# nChannel.net
KiCad netlist of a schematic drawn in EAGLE
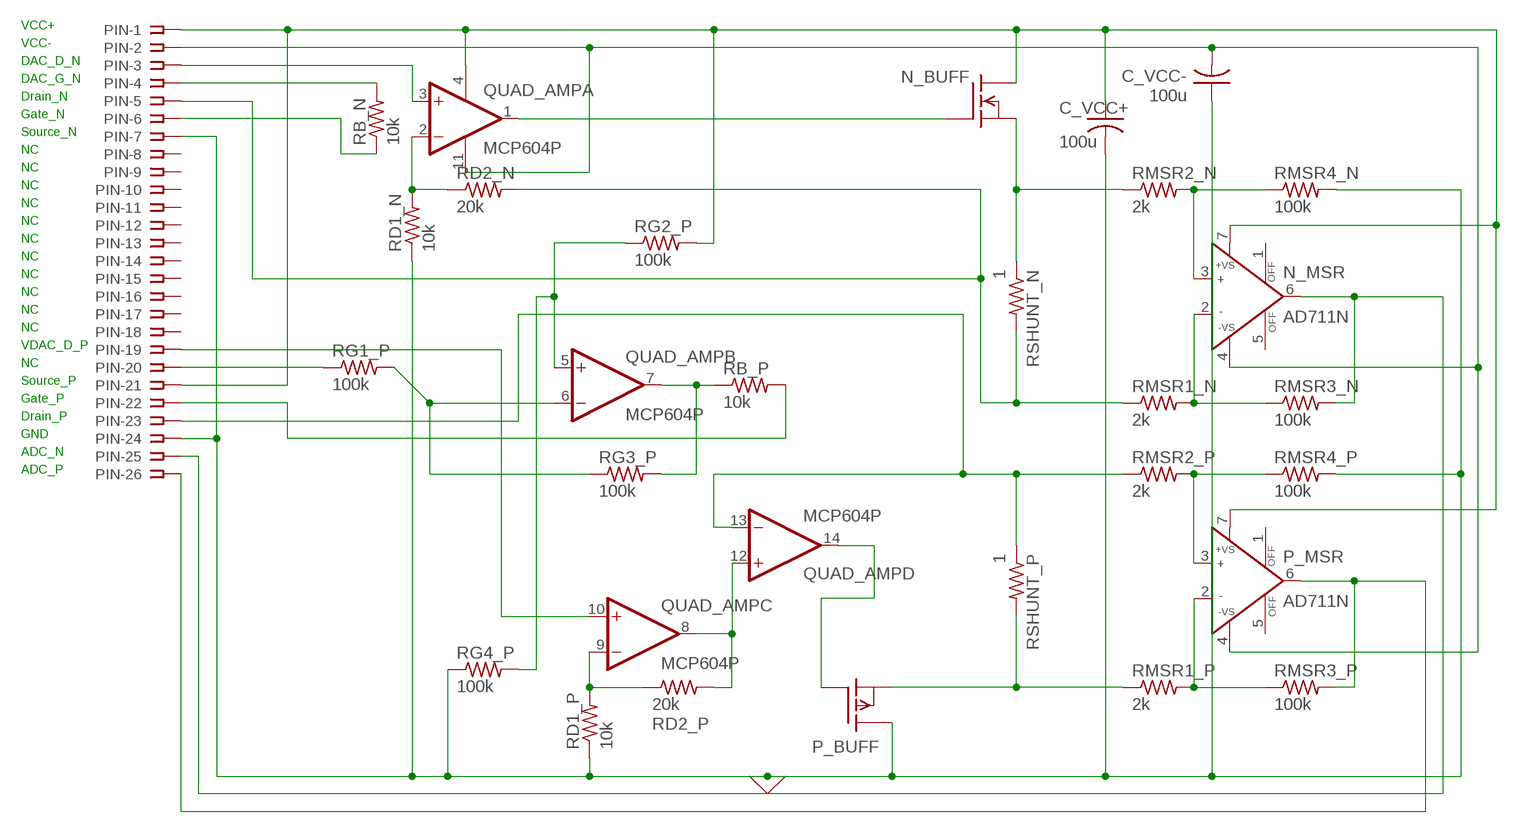
[diagram p0: schematic, sheet 1]

(export (version "E")
  (design (tool "Eeschema 10.0.6"))
  (components
    (comp (ref "C_VCC+")
      (value "100u")
      (footprint "eagle-import:C025-024X044")
      (libsource (lib "eagle-import") (part "C-US025-024X044"))
    )
    (comp (ref "C_VCC-")
      (value "100u")
      (footprint "eagle-import:C025-024X044")
      (libsource (lib "eagle-import") (part "C-US025-024X044"))
    )
    (comp (ref "N_BUFF")
      (value "BSS101")
      (footprint "eagle-import:TO92")
      (libsource (lib "eagle-import") (part "BSS101"))
    )
    (comp (ref "N_MSR")
      (value "AD711N")
      (footprint "eagle-import:DIL08")
      (fields (field (name "MPN") "AD711BQ"))
      (libsource (lib "eagle-import") (part "AD711N"))
    )
    (comp (ref "PIN")
      (value "SSW-126-02-G-S")
      (footprint "eagle-import:SSW-126-02-G-S")
      (fields (field (name "MF") "Samtec Inc."))
      (libsource (lib "eagle-import") (part "SSW-126-02-G-S"))
    )
    (comp (ref "P_BUFF")
      (value "BSS110")
      (footprint "eagle-import:TO92")
      (libsource (lib "eagle-import") (part "BSS110"))
    )
    (comp (ref "P_MSR")
      (value "AD711N")
      (footprint "eagle-import:DIL08")
      (fields (field (name "MPN") "AD711BQ"))
      (libsource (lib "eagle-import") (part "AD711N"))
    )
    (comp (ref "QUAD_AMP")
      (value "MCP604P")
      (footprint "eagle-import:DIL14")
      (libsource (lib "eagle-import") (part "MCP604P"))
    )
    (comp (ref "RB_N")
      (value "10k")
      (footprint "eagle-import:0204_5")
      (libsource (lib "eagle-import") (part "R-US_0204/5"))
    )
    (comp (ref "RB_P")
      (value "10k")
      (footprint "eagle-import:0204_5")
      (libsource (lib "eagle-import") (part "R-US_0204/5"))
    )
    (comp (ref "RD1_N")
      (value "10k")
      (footprint "eagle-import:0204_5")
      (libsource (lib "eagle-import") (part "R-US_0204/5"))
    )
    (comp (ref "RD1_P")
      (value "10k")
      (footprint "eagle-import:0204_5")
      (libsource (lib "eagle-import") (part "R-US_0204/5"))
    )
    (comp (ref "RD2_N")
      (value "20k")
      (footprint "eagle-import:0204_5")
      (libsource (lib "eagle-import") (part "R-US_0204/5"))
    )
    (comp (ref "RD2_P")
      (value "20k")
      (footprint "eagle-import:0204_5")
      (libsource (lib "eagle-import") (part "R-US_0204/5"))
    )
    (comp (ref "RG1_P")
      (value "100k")
      (footprint "eagle-import:0204_5")
      (libsource (lib "eagle-import") (part "R-US_0204/5"))
    )
    (comp (ref "RG2_P")
      (value "100k")
      (footprint "eagle-import:0204_5")
      (libsource (lib "eagle-import") (part "R-US_0204/5"))
    )
    (comp (ref "RG3_P")
      (value "100k")
      (footprint "eagle-import:0204_5")
      (libsource (lib "eagle-import") (part "R-US_0204/5"))
    )
    (comp (ref "RG4_P")
      (value "100k")
      (footprint "eagle-import:0204_5")
      (libsource (lib "eagle-import") (part "R-US_0204/5"))
    )
    (comp (ref "RMSR1_N")
      (value "2k")
      (footprint "eagle-import:0204_5")
      (libsource (lib "eagle-import") (part "R-US_0204/5"))
    )
    (comp (ref "RMSR1_P")
      (value "2k")
      (footprint "eagle-import:0204_5")
      (libsource (lib "eagle-import") (part "R-US_0204/5"))
    )
    (comp (ref "RMSR2_N")
      (value "2k")
      (footprint "eagle-import:0204_5")
      (libsource (lib "eagle-import") (part "R-US_0204/5"))
    )
    (comp (ref "RMSR2_P")
      (value "2k")
      (footprint "eagle-import:0204_5")
      (libsource (lib "eagle-import") (part "R-US_0204/5"))
    )
    (comp (ref "RMSR3_N")
      (value "100k")
      (footprint "eagle-import:0204_5")
      (libsource (lib "eagle-import") (part "R-US_0204/5"))
    )
    (comp (ref "RMSR3_P")
      (value "100k")
      (footprint "eagle-import:0204_5")
      (libsource (lib "eagle-import") (part "R-US_0204/5"))
    )
    (comp (ref "RMSR4_N")
      (value "100k")
      (footprint "eagle-import:0204_5")
      (libsource (lib "eagle-import") (part "R-US_0204/5"))
    )
    (comp (ref "RMSR4_P")
      (value "100k")
      (footprint "eagle-import:0204_5")
      (libsource (lib "eagle-import") (part "R-US_0204/5"))
    )
    (comp (ref "RSHUNT_N")
      (value "1")
      (footprint "eagle-import:0204_5")
      (fields (field (name "SPICEPREFIX") "52"))
      (libsource (lib "eagle-import") (part "R-US_0204/5"))
    )
    (comp (ref "RSHUNT_P")
      (value "1")
      (footprint "eagle-import:0204_5")
      (fields (field (name "SPICEPREFIX") "52"))
      (libsource (lib "eagle-import") (part "R-US_0204/5"))
    )
  )
  (nets
    (net (code "1") (name "GND") (class "Default")
      (node (ref "C_VCC+") (pin "2") (pinfunction "2_2") (pintype "passive"))
      (node (ref "C_VCC-") (pin "1") (pinfunction "1_1") (pintype "passive"))
      (node (ref "PIN") (pin "24") (pinfunction "1_24") (pintype "passive"))
      (node (ref "PIN") (pin "7") (pinfunction "1_7") (pintype "passive"))
      (node (ref "P_BUFF") (pin "3") (pinfunction "D_3") (pintype "passive"))
      (node (ref "RD1_N") (pin "1") (pinfunction "1_1") (pintype "passive"))
      (node (ref "RD1_P") (pin "1") (pinfunction "1_1") (pintype "passive"))
      (node (ref "RG4_P") (pin "1") (pinfunction "1_1") (pintype "passive"))
      (node (ref "RMSR4_N") (pin "2") (pinfunction "2_2") (pintype "passive"))
      (node (ref "RMSR4_P") (pin "2") (pinfunction "2_2") (pintype "passive"))
    )
    (net (code "2") (name "Net-(N_BUFF-D)") (class "Default")
      (node (ref "C_VCC+") (pin "1") (pinfunction "1_1") (pintype "passive"))
      (node (ref "N_BUFF") (pin "3") (pinfunction "D_3") (pintype "passive"))
      (node (ref "N_MSR") (pin "7") (pinfunction "+VS_7") (pintype "input"))
      (node (ref "PIN") (pin "1") (pinfunction "1_1") (pintype "passive"))
      (node (ref "PIN") (pin "21") (pinfunction "1_21") (pintype "passive"))
      (node (ref "P_MSR") (pin "7") (pinfunction "+VS_7") (pintype "input"))
      (node (ref "QUAD_AMP") (pin "4") (pinfunction "V+_4") (pintype "power_in"))
      (node (ref "RG2_P") (pin "2") (pinfunction "2_2") (pintype "passive"))
    )
    (net (code "3") (name "Net-(N_BUFF-G)") (class "Default")
      (node (ref "N_BUFF") (pin "2") (pinfunction "G_2") (pintype "passive"))
      (node (ref "QUAD_AMP") (pin "1") (pinfunction "OUT_1") (pintype "output"))
    )
    (net (code "4") (name "Net-(N_BUFF-S)") (class "Default")
      (node (ref "N_BUFF") (pin "1") (pinfunction "S_1") (pintype "passive"))
      (node (ref "RMSR2_N") (pin "1") (pinfunction "1_1") (pintype "passive"))
      (node (ref "RSHUNT_N") (pin "1") (pinfunction "1_1") (pintype "passive"))
    )
    (net (code "5") (name "Net-(N_MSR--VS)") (class "Default")
      (node (ref "C_VCC-") (pin "2") (pinfunction "2_2") (pintype "passive"))
      (node (ref "N_MSR") (pin "4") (pinfunction "-VS_4") (pintype "input"))
      (node (ref "PIN") (pin "2") (pinfunction "1_2") (pintype "passive"))
      (node (ref "P_MSR") (pin "4") (pinfunction "-VS_4") (pintype "input"))
      (node (ref "QUAD_AMP") (pin "11") (pinfunction "V-_11") (pintype "power_in"))
    )
    (net (code "6") (name "Net-(N_MSR-IN+)") (class "Default")
      (node (ref "N_MSR") (pin "3") (pinfunction "IN+_3") (pintype "input"))
      (node (ref "RMSR2_N") (pin "2") (pinfunction "2_2") (pintype "passive"))
      (node (ref "RMSR4_N") (pin "1") (pinfunction "1_1") (pintype "passive"))
    )
    (net (code "7") (name "Net-(N_MSR-IN-)") (class "Default")
      (node (ref "N_MSR") (pin "2") (pinfunction "IN-_2") (pintype "input"))
      (node (ref "RMSR1_N") (pin "2") (pinfunction "2_2") (pintype "passive"))
      (node (ref "RMSR3_N") (pin "1") (pinfunction "1_1") (pintype "passive"))
    )
    (net (code "8") (name "Net-(N_MSR-OUT)") (class "Default")
      (node (ref "N_MSR") (pin "6") (pinfunction "OUT_6") (pintype "output"))
      (node (ref "PIN") (pin "25") (pinfunction "1_25") (pintype "passive"))
      (node (ref "RMSR3_N") (pin "2") (pinfunction "2_2") (pintype "passive"))
    )
    (net (code "9") (name "Net-(PINK-1)") (class "Default")
      (node (ref "PIN") (pin "19") (pinfunction "1_19") (pintype "passive"))
      (node (ref "QUAD_AMP") (pin "10") (pinfunction "+IN_10") (pintype "input"))
    )
    (net (code "10") (name "Net-(PINM-1)") (class "Default")
      (node (ref "PIN") (pin "20") (pinfunction "1_20") (pintype "passive"))
      (node (ref "RG1_P") (pin "1") (pinfunction "1_1") (pintype "passive"))
    )
    (net (code "11") (name "Net-(PINO-1)") (class "Default")
      (node (ref "PIN") (pin "22") (pinfunction "1_22") (pintype "passive"))
      (node (ref "RB_P") (pin "2") (pinfunction "2_2") (pintype "passive"))
    )
    (net (code "12") (name "Net-(PINP-1)") (class "Default")
      (node (ref "PIN") (pin "23") (pinfunction "1_23") (pintype "passive"))
      (node (ref "QUAD_AMP") (pin "13") (pinfunction "-IN_13") (pintype "input"))
      (node (ref "RMSR2_P") (pin "1") (pinfunction "1_1") (pintype "passive"))
      (node (ref "RSHUNT_P") (pin "1") (pinfunction "1_1") (pintype "passive"))
    )
    (net (code "13") (name "Net-(PINS-1)") (class "Default")
      (node (ref "PIN") (pin "26") (pinfunction "1_26") (pintype "passive"))
      (node (ref "P_MSR") (pin "6") (pinfunction "OUT_6") (pintype "output"))
      (node (ref "RMSR3_P") (pin "2") (pinfunction "2_2") (pintype "passive"))
    )
    (net (code "14") (name "Net-(PINT-1)") (class "Default")
      (node (ref "PIN") (pin "3") (pinfunction "1_3") (pintype "passive"))
      (node (ref "QUAD_AMP") (pin "3") (pinfunction "+IN_3") (pintype "input"))
    )
    (net (code "15") (name "Net-(PINU-1)") (class "Default")
      (node (ref "PIN") (pin "4") (pinfunction "1_4") (pintype "passive"))
      (node (ref "RB_N") (pin "2") (pinfunction "2_2") (pintype "passive"))
    )
    (net (code "16") (name "Net-(PINV-1)") (class "Default")
      (node (ref "PIN") (pin "5") (pinfunction "1_5") (pintype "passive"))
      (node (ref "RD2_N") (pin "2") (pinfunction "2_2") (pintype "passive"))
      (node (ref "RMSR1_N") (pin "1") (pinfunction "1_1") (pintype "passive"))
      (node (ref "RSHUNT_N") (pin "2") (pinfunction "2_2") (pintype "passive"))
    )
    (net (code "17") (name "Net-(PINW-1)") (class "Default")
      (node (ref "PIN") (pin "6") (pinfunction "1_6") (pintype "passive"))
      (node (ref "RB_N") (pin "1") (pinfunction "1_1") (pintype "passive"))
    )
    (net (code "18") (name "Net-(P_BUFF-G)") (class "Default")
      (node (ref "P_BUFF") (pin "2") (pinfunction "G_2") (pintype "passive"))
      (node (ref "QUAD_AMP") (pin "14") (pinfunction "OUT_14") (pintype "output"))
    )
    (net (code "19") (name "Net-(P_BUFF-S)") (class "Default")
      (node (ref "P_BUFF") (pin "1") (pinfunction "S_1") (pintype "passive"))
      (node (ref "RMSR1_P") (pin "1") (pinfunction "1_1") (pintype "passive"))
      (node (ref "RSHUNT_P") (pin "2") (pinfunction "2_2") (pintype "passive"))
    )
    (net (code "20") (name "Net-(P_MSR-IN+)") (class "Default")
      (node (ref "P_MSR") (pin "3") (pinfunction "IN+_3") (pintype "input"))
      (node (ref "RMSR2_P") (pin "2") (pinfunction "2_2") (pintype "passive"))
      (node (ref "RMSR4_P") (pin "1") (pinfunction "1_1") (pintype "passive"))
    )
    (net (code "21") (name "Net-(P_MSR-IN-)") (class "Default")
      (node (ref "P_MSR") (pin "2") (pinfunction "IN-_2") (pintype "input"))
      (node (ref "RMSR1_P") (pin "2") (pinfunction "2_2") (pintype "passive"))
      (node (ref "RMSR3_P") (pin "1") (pinfunction "1_1") (pintype "passive"))
    )
    (net (code "22") (name "Net-(QUAD_AMPA--IN)") (class "Default")
      (node (ref "QUAD_AMP") (pin "2") (pinfunction "-IN_2") (pintype "input"))
      (node (ref "RD1_N") (pin "2") (pinfunction "2_2") (pintype "passive"))
      (node (ref "RD2_N") (pin "1") (pinfunction "1_1") (pintype "passive"))
    )
    (net (code "23") (name "Net-(QUAD_AMPB-+IN)") (class "Default")
      (node (ref "QUAD_AMP") (pin "5") (pinfunction "+IN_5") (pintype "input"))
      (node (ref "RG2_P") (pin "1") (pinfunction "1_1") (pintype "passive"))
      (node (ref "RG4_P") (pin "2") (pinfunction "2_2") (pintype "passive"))
    )
    (net (code "24") (name "Net-(QUAD_AMPB--IN)") (class "Default")
      (node (ref "QUAD_AMP") (pin "6") (pinfunction "-IN_6") (pintype "input"))
      (node (ref "RG1_P") (pin "2") (pinfunction "2_2") (pintype "passive"))
      (node (ref "RG3_P") (pin "1") (pinfunction "1_1") (pintype "passive"))
    )
    (net (code "25") (name "Net-(QUAD_AMPB-OUT)") (class "Default")
      (node (ref "QUAD_AMP") (pin "7") (pinfunction "OUT_7") (pintype "output"))
      (node (ref "RB_P") (pin "1") (pinfunction "1_1") (pintype "passive"))
      (node (ref "RG3_P") (pin "2") (pinfunction "2_2") (pintype "passive"))
    )
    (net (code "26") (name "Net-(QUAD_AMPC--IN)") (class "Default")
      (node (ref "QUAD_AMP") (pin "9") (pinfunction "-IN_9") (pintype "input"))
      (node (ref "RD1_P") (pin "2") (pinfunction "2_2") (pintype "passive"))
      (node (ref "RD2_P") (pin "1") (pinfunction "1_1") (pintype "passive"))
    )
    (net (code "27") (name "Net-(QUAD_AMPC-OUT)") (class "Default")
      (node (ref "QUAD_AMP") (pin "12") (pinfunction "+IN_12") (pintype "input"))
      (node (ref "QUAD_AMP") (pin "8") (pinfunction "OUT_8") (pintype "output"))
      (node (ref "RD2_P") (pin "2") (pinfunction "2_2") (pintype "passive"))
    )
    (net (code "28") (name "unconnected-(N_MSR-OFF-Pad1)") (class "Default")
      (node (ref "N_MSR") (pin "1") (pinfunction "OFF_1") (pintype "passive"))
    )
    (net (code "29") (name "unconnected-(N_MSR-OFF-Pad5)") (class "Default")
      (node (ref "N_MSR") (pin "5") (pinfunction "OFF_5") (pintype "passive"))
    )
    (net (code "30") (name "unconnected-(PINB-1-Pad10)") (class "Default")
      (node (ref "PIN") (pin "10") (pinfunction "1_10") (pintype "passive"))
    )
    (net (code "31") (name "unconnected-(PINC-1-Pad11)") (class "Default")
      (node (ref "PIN") (pin "11") (pinfunction "1_11") (pintype "passive"))
    )
    (net (code "32") (name "unconnected-(PIND-1-Pad12)") (class "Default")
      (node (ref "PIN") (pin "12") (pinfunction "1_12") (pintype "passive"))
    )
    (net (code "33") (name "unconnected-(PINE-1-Pad13)") (class "Default")
      (node (ref "PIN") (pin "13") (pinfunction "1_13") (pintype "passive"))
    )
    (net (code "34") (name "unconnected-(PINF-1-Pad14)") (class "Default")
      (node (ref "PIN") (pin "14") (pinfunction "1_14") (pintype "passive"))
    )
    (net (code "35") (name "unconnected-(PING-1-Pad15)") (class "Default")
      (node (ref "PIN") (pin "15") (pinfunction "1_15") (pintype "passive"))
    )
    (net (code "36") (name "unconnected-(PINH-1-Pad16)") (class "Default")
      (node (ref "PIN") (pin "16") (pinfunction "1_16") (pintype "passive"))
    )
    (net (code "37") (name "unconnected-(PINI-1-Pad17)") (class "Default")
      (node (ref "PIN") (pin "17") (pinfunction "1_17") (pintype "passive"))
    )
    (net (code "38") (name "unconnected-(PINJ-1-Pad18)") (class "Default")
      (node (ref "PIN") (pin "18") (pinfunction "1_18") (pintype "passive"))
    )
    (net (code "39") (name "unconnected-(PINY-1-Pad8)") (class "Default")
      (node (ref "PIN") (pin "8") (pinfunction "1_8") (pintype "passive"))
    )
    (net (code "40") (name "unconnected-(PINZ-1-Pad9)") (class "Default")
      (node (ref "PIN") (pin "9") (pinfunction "1_9") (pintype "passive"))
    )
    (net (code "41") (name "unconnected-(P_MSR-OFF-Pad1)") (class "Default")
      (node (ref "P_MSR") (pin "1") (pinfunction "OFF_1") (pintype "passive"))
    )
    (net (code "42") (name "unconnected-(P_MSR-OFF-Pad5)") (class "Default")
      (node (ref "P_MSR") (pin "5") (pinfunction "OFF_5") (pintype "passive"))
    )
  )
)
